# ADC.net
KiCad netlist of a schematic drawn in Altium Designer
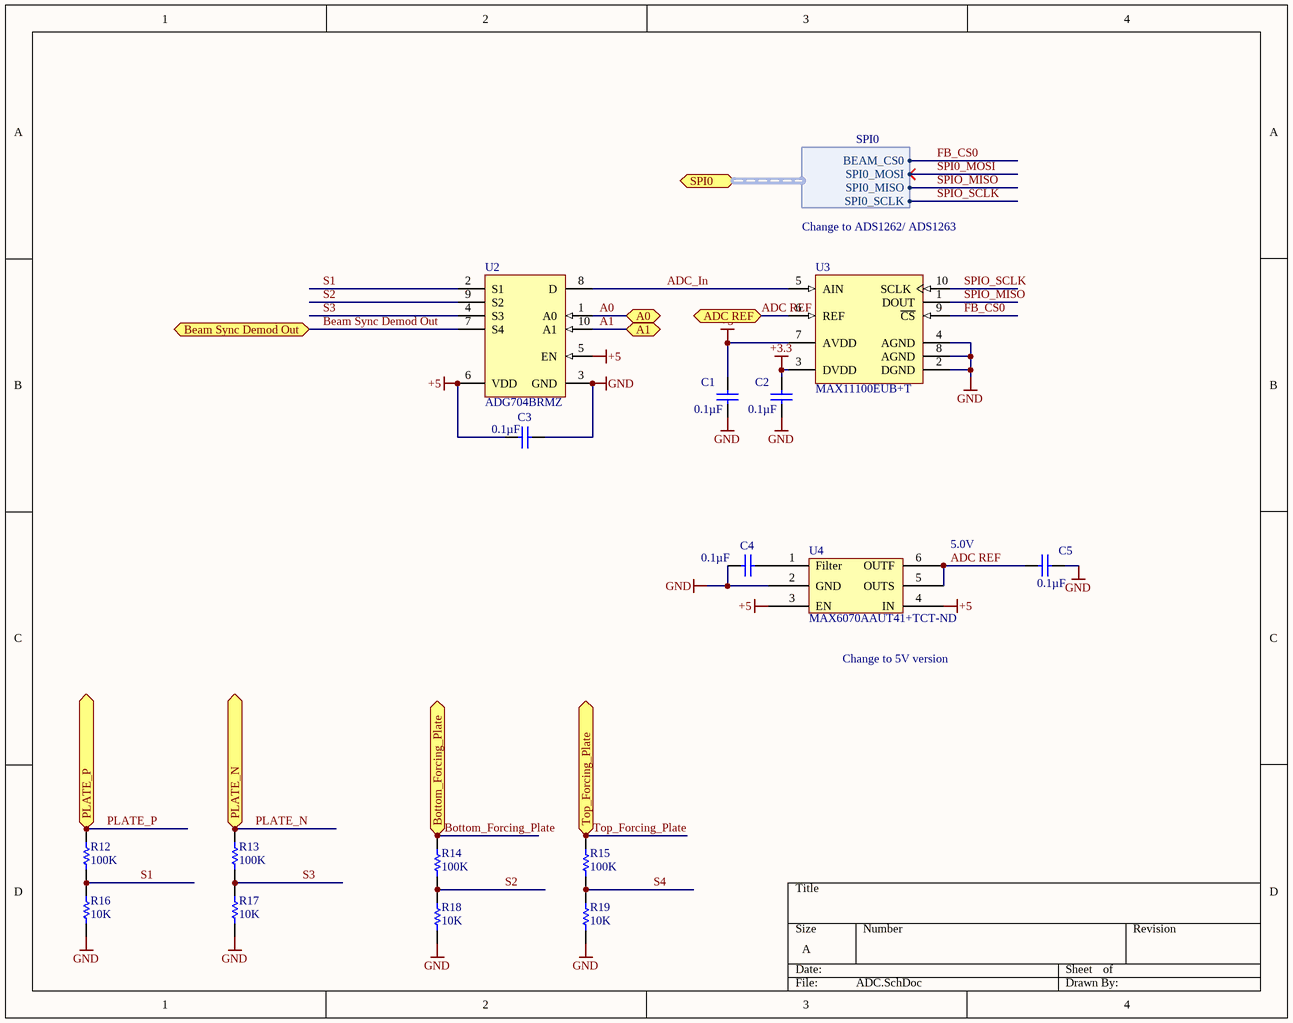
[diagram p0: ADC.SchDoc]

(export (version "E")
  (design (tool "Eeschema 10.0.6"))
  (components
    (comp (ref "C1")
      (value "CAP CER 0.1UF 25V X7R 0805")
      (footprint "CAPC0805(2012)145_N")
      (fields
        (field (name "MANUFACTURER") "Murata Electronics North America")
        (field (name "MANUFACTURER PART NUMBER") "GRM21BR71E104KA01L")
        (field (name "CAPACITANCE") "0.1µF")
        (field (name "TOLERANCE") "±10%")
      )
      (libsource (lib "Altium Content Vault") (part "CMP-1036-04795-1"))
    )
    (comp (ref "C2")
      (value "CAP CER 0.1UF 25V X7R 0805")
      (footprint "CAPC0805(2012)145_N")
      (fields
        (field (name "MANUFACTURER") "Murata Electronics North America")
        (field (name "MANUFACTURER PART NUMBER") "GRM21BR71E104KA01L")
        (field (name "CAPACITANCE") "0.1µF")
        (field (name "TOLERANCE") "±10%")
      )
      (libsource (lib "Altium Content Vault") (part "CMP-1036-04795-1"))
    )
    (comp (ref "C3")
      (value "CAP CER 0.1UF 25V X7R 0805")
      (footprint "CAPC0805(2012)145_N")
      (fields
        (field (name "MANUFACTURER") "Murata Electronics North America")
        (field (name "MANUFACTURER PART NUMBER") "GRM21BR71E104KA01L")
        (field (name "CAPACITANCE") "0.1µF")
        (field (name "TOLERANCE") "±10%")
      )
      (libsource (lib "Altium Content Vault") (part "CMP-1036-04795-1"))
    )
    (comp (ref "C4")
      (value "CAP CER 0.1UF 25V X7R 0805")
      (footprint "CAPC0805(2012)145_N")
      (fields
        (field (name "MANUFACTURER") "Murata Electronics North America")
        (field (name "MANUFACTURER PART NUMBER") "GRM21BR71E104KA01L")
        (field (name "CAPACITANCE") "0.1µF")
        (field (name "TOLERANCE") "±10%")
      )
      (libsource (lib "Altium Content Vault") (part "CMP-1036-04795-1"))
    )
    (comp (ref "C5")
      (value "CAP CER 0.1UF 25V X7R 0805")
      (footprint "CAPC0805(2012)145_N")
      (fields
        (field (name "MANUFACTURER") "Murata Electronics North America")
        (field (name "MANUFACTURER PART NUMBER") "GRM21BR71E104KA01L")
        (field (name "CAPACITANCE") "0.1µF")
        (field (name "TOLERANCE") "±10%")
      )
      (libsource (lib "Altium Content Vault") (part "CMP-1036-04795-1"))
    )
    (comp (ref "R12")
      (value "100K")
      (footprint "RESC0402(1005)_M")
      (libsource (lib "Altium Content Vault") (part "CMP-1011-00463-1"))
    )
    (comp (ref "R13")
      (value "100K")
      (footprint "RESC0402(1005)_M")
      (libsource (lib "Altium Content Vault") (part "CMP-1011-00463-1"))
    )
    (comp (ref "R14")
      (value "100K")
      (footprint "RESC0402(1005)_M")
      (libsource (lib "Altium Content Vault") (part "CMP-1011-00463-1"))
    )
    (comp (ref "R15")
      (value "100K")
      (footprint "RESC0402(1005)_M")
      (libsource (lib "Altium Content Vault") (part "CMP-1011-00463-1"))
    )
    (comp (ref "R16")
      (value "10K")
      (footprint "RESC0402(1005)_M")
      (libsource (lib "Altium Content Vault") (part "CMP-1011-00463-1"))
    )
    (comp (ref "R17")
      (value "10K")
      (footprint "RESC0402(1005)_M")
      (libsource (lib "Altium Content Vault") (part "CMP-1011-00463-1"))
    )
    (comp (ref "R18")
      (value "10K")
      (footprint "RESC0402(1005)_M")
      (libsource (lib "Altium Content Vault") (part "CMP-1011-00463-1"))
    )
    (comp (ref "R19")
      (value "10K")
      (footprint "RESC0402(1005)_M")
      (libsource (lib "Altium Content Vault") (part "CMP-1011-00463-1"))
    )
    (comp (ref "U2")
      (value "ADG704BRMZ")
      (footprint "ADI-RM-10_L")
      (description "CMOS Low Voltage 4 Ohm, 4-Channel Multiplexer, -40 to 85 degC, 10-pin SOP (RM-10), Tube")
      (fields (field (name "MANUFACTURER") "Analog Devices"))
      (libsource (lib "Altium Content Vault") (part "ADI-ADG704-RM-10"))
    )
    (comp (ref "U3")
      (value "MAX11100EUB+T")
      (footprint "U10+2_L")
      (description "16-Bit, +5V, 200ksps ADC with 10uA Shutdown, 10-Pin uMAX, -40°C to +85°C, Pb-Free, Tape and Reel")
      (fields
        (field (name "MANUFACTURER") "Maxim Integrated")
        (field (name "MANUFACTURER PART NUMBER") "MAX11100EUB+")
      )
      (libsource (lib "Altium Content Vault") (part "CMP-0249-00017-1"))
    )
    (comp (ref "U4")
      (value "MAX6070AAUT41+T")
      (footprint "SOT95P280X445-6N")
      (description "IC VREF SERIES 4.096V SOT23")
      (fields
        (field (name "SUPPLIER PART NUMBER 1") "MAX6070AAUT41+TCT-ND")
        (field (name "MANUFACTURER") "Maxim Integrated")
        (field (name "TOLERANCE") "±0.04%")
      )
      (libsource (lib "ZLS_Schematic_lib") (part "MAX6070AAUT41+T"))
    )
  )
  (nets
    (net (code "2") (name "+3.3") (class "Default")
      (node (ref "C2") (pin "1") (pinfunction "1_1") (pintype "passive"))
      (node (ref "U3") (pin "3") (pinfunction "DVDD_3") (pintype "power_in"))
    )
    (net (code "3") (name "+5") (class "Default")
      (node (ref "C1") (pin "1") (pinfunction "1_1") (pintype "passive"))
      (node (ref "C3") (pin "1") (pinfunction "1_1") (pintype "passive"))
      (node (ref "U2") (pin "5") (pinfunction "EN_5") (pintype "input"))
      (node (ref "U2") (pin "6") (pinfunction "VDD_6") (pintype "power_in"))
      (node (ref "U3") (pin "7") (pinfunction "AVDD_7") (pintype "power_in"))
      (node (ref "U4") (pin "3") (pinfunction "EN_3") (pintype "passive"))
      (node (ref "U4") (pin "4") (pinfunction "IN_4") (pintype "passive"))
    )
    (net (code "4") (name "/A0") (class "Default")
      (node (ref "U2") (pin "1") (pinfunction "A0_1") (pintype "input"))
    )
    (net (code "5") (name "/A1") (class "Default")
      (node (ref "U2") (pin "10") (pinfunction "A1_10") (pintype "input"))
    )
    (net (code "6") (name "/ADC REF") (class "Default")
      (node (ref "C5") (pin "1") (pinfunction "1_1") (pintype "passive"))
      (node (ref "U3") (pin "6") (pinfunction "REF_6") (pintype "input"))
      (node (ref "U4") (pin "5") (pinfunction "OUTS_5") (pintype "passive"))
      (node (ref "U4") (pin "6") (pinfunction "OUTF_6") (pintype "passive"))
    )
    (net (code "7") (name "/ADC_In") (class "Default")
      (node (ref "U2") (pin "8") (pinfunction "D_8") (pintype "passive"))
      (node (ref "U3") (pin "5") (pinfunction "AIN_5") (pintype "input"))
    )
    (net (code "8") (name "/Beam Sync Demod Out") (class "Default")
      (node (ref "U2") (pin "7") (pinfunction "S4_7") (pintype "passive"))
    )
    (net (code "9") (name "/Bottom_Forcing_Plate") (class "Default")
      (node (ref "R14") (pin "2") (pinfunction "2_2") (pintype "passive"))
    )
    (net (code "10") (name "/FB_CS0") (class "Default")
      (node (ref "U3") (pin "9") (pinfunction "~{CS}_9") (pintype "input"))
    )
    (net (code "11") (name "/PLATE_N") (class "Default")
      (node (ref "R13") (pin "2") (pinfunction "2_2") (pintype "passive"))
    )
    (net (code "12") (name "/PLATE_P") (class "Default")
      (node (ref "R12") (pin "2") (pinfunction "2_2") (pintype "passive"))
    )
    (net (code "13") (name "/S1") (class "Default")
      (node (ref "R12") (pin "1") (pinfunction "1_1") (pintype "passive"))
      (node (ref "R16") (pin "2") (pinfunction "2_2") (pintype "passive"))
      (node (ref "U2") (pin "2") (pinfunction "S1_2") (pintype "passive"))
    )
    (net (code "14") (name "/S2") (class "Default")
      (node (ref "R14") (pin "1") (pinfunction "1_1") (pintype "passive"))
      (node (ref "R18") (pin "2") (pinfunction "2_2") (pintype "passive"))
      (node (ref "U2") (pin "9") (pinfunction "S2_9") (pintype "passive"))
    )
    (net (code "15") (name "/S3") (class "Default")
      (node (ref "R13") (pin "1") (pinfunction "1_1") (pintype "passive"))
      (node (ref "R17") (pin "2") (pinfunction "2_2") (pintype "passive"))
      (node (ref "U2") (pin "4") (pinfunction "S3_4") (pintype "passive"))
    )
    (net (code "16") (name "/S4") (class "Default")
      (node (ref "R15") (pin "1") (pinfunction "1_1") (pintype "passive"))
      (node (ref "R19") (pin "2") (pinfunction "2_2") (pintype "passive"))
    )
    (net (code "18") (name "/SPIO_MISO") (class "Default")
      (node (ref "U3") (pin "1") (pinfunction "DOUT_1") (pintype "tri_state"))
    )
    (net (code "19") (name "/SPIO_SCLK") (class "Default")
      (node (ref "U3") (pin "10") (pinfunction "SCLK_10") (pintype "input"))
    )
    (net (code "20") (name "/Top_Forcing_Plate") (class "Default")
      (node (ref "R15") (pin "2") (pinfunction "2_2") (pintype "passive"))
    )
    (net (code "22") (name "GND") (class "Default")
      (node (ref "C1") (pin "2") (pinfunction "2_2") (pintype "passive"))
      (node (ref "C2") (pin "2") (pinfunction "2_2") (pintype "passive"))
      (node (ref "C3") (pin "2") (pinfunction "2_2") (pintype "passive"))
      (node (ref "C4") (pin "1") (pinfunction "1_1") (pintype "passive"))
      (node (ref "C5") (pin "2") (pinfunction "2_2") (pintype "passive"))
      (node (ref "R16") (pin "1") (pinfunction "1_1") (pintype "passive"))
      (node (ref "R17") (pin "1") (pinfunction "1_1") (pintype "passive"))
      (node (ref "R18") (pin "1") (pinfunction "1_1") (pintype "passive"))
      (node (ref "R19") (pin "1") (pinfunction "1_1") (pintype "passive"))
      (node (ref "U2") (pin "3") (pinfunction "GND_3") (pintype "power_in"))
      (node (ref "U3") (pin "2") (pinfunction "DGND_2") (pintype "power_in"))
      (node (ref "U3") (pin "4") (pinfunction "AGND_4") (pintype "power_in"))
      (node (ref "U3") (pin "8") (pinfunction "AGND_8") (pintype "power_in"))
      (node (ref "U4") (pin "2") (pinfunction "GND_2") (pintype "passive"))
    )
    (net (code "23") (name "Net-(U4-Filter)") (class "Default")
      (node (ref "C4") (pin "2") (pinfunction "2_2") (pintype "passive"))
      (node (ref "U4") (pin "1") (pinfunction "Filter_1") (pintype "passive"))
    )
  )
)
